# paw.net
KiCad netlist of a schematic drawn in EAGLE
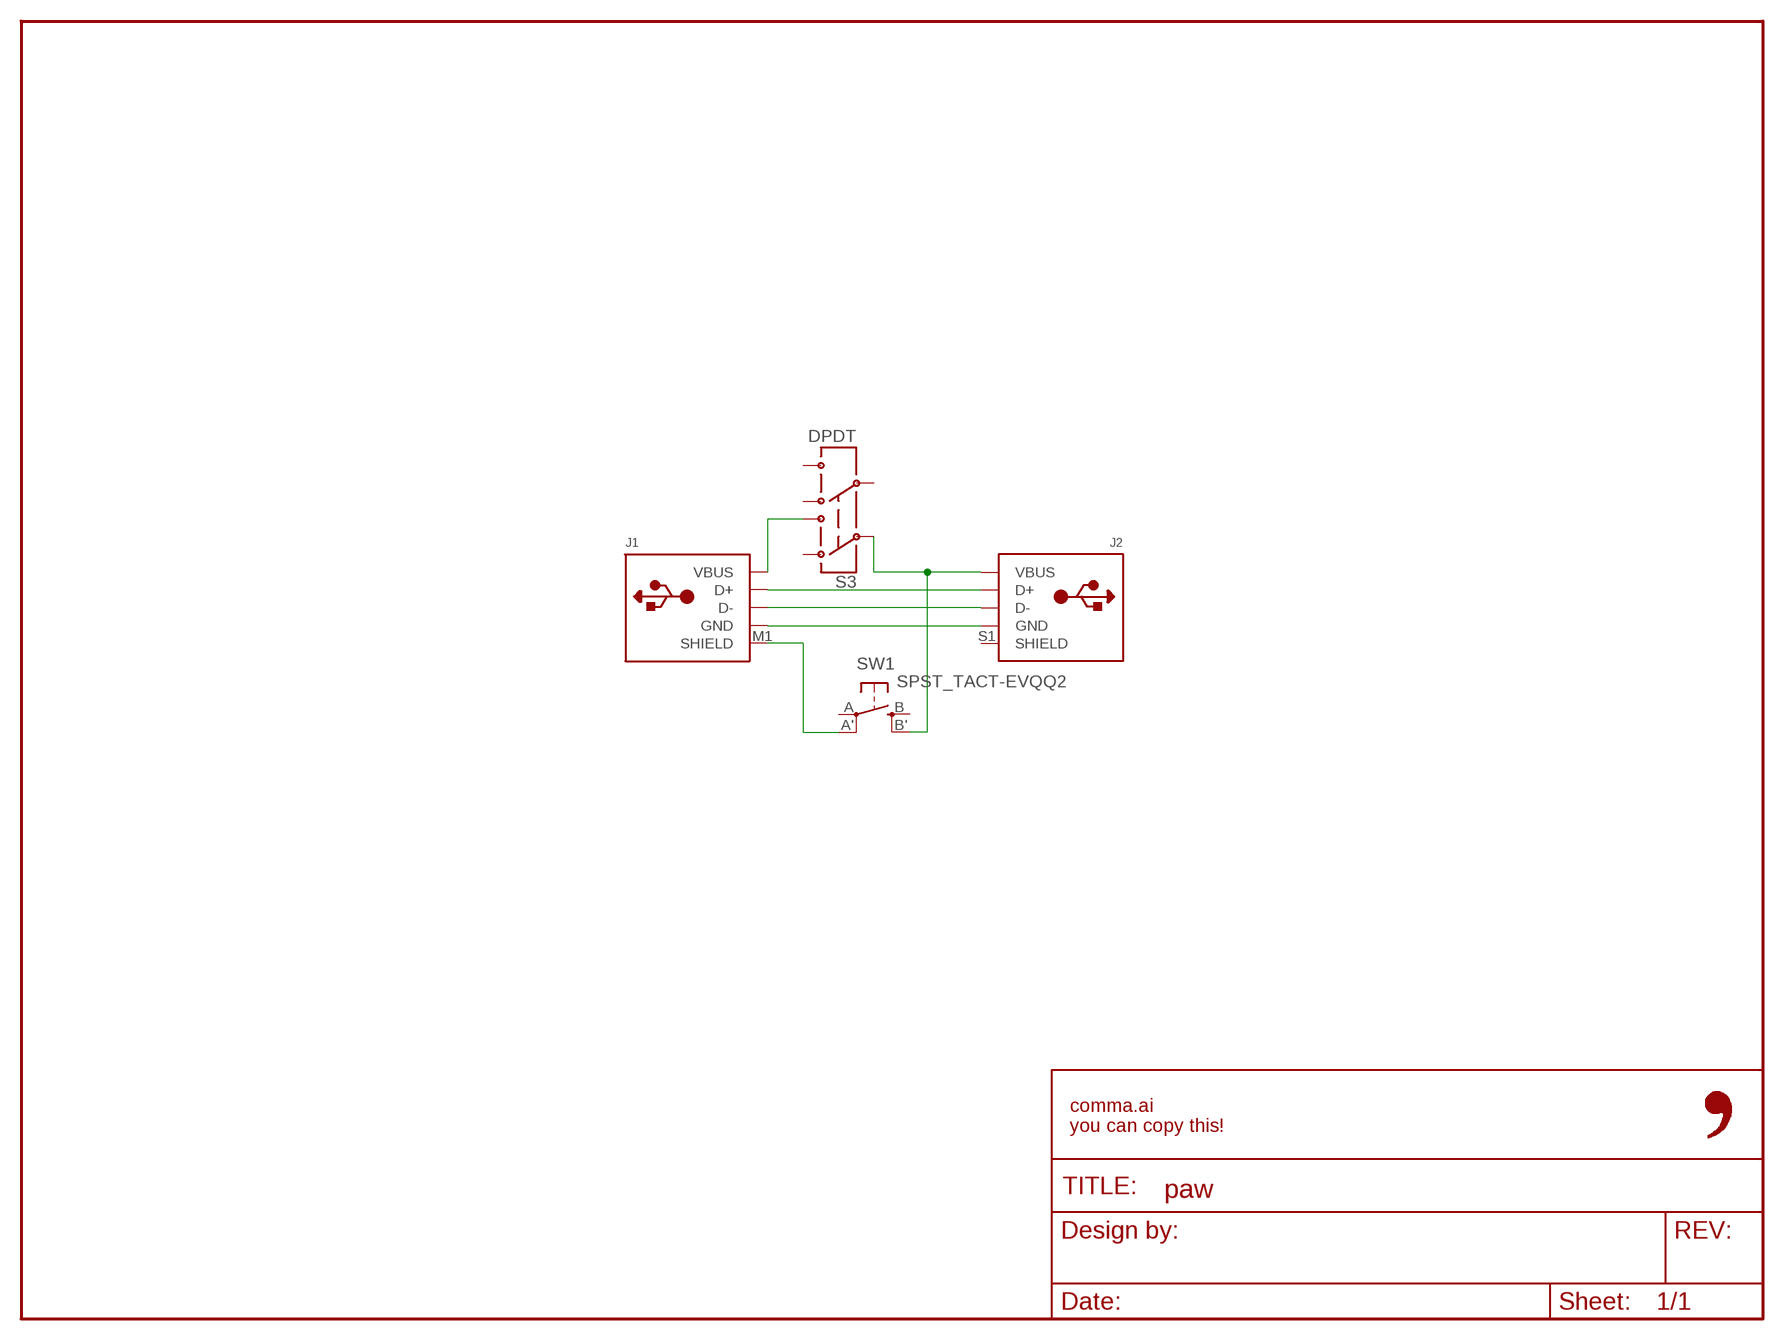
[diagram p0: schematic, sheet 1]

(export (version "E")
  (design (tool "Eeschema 10.0.6"))
  (components
    (comp (ref "FRAME1")
      (value "FRAME-LETTER-OPENNO_PACKAGE")
      (footprint "eagle-import:DUMMY")
      (fields (field (name "DESIGNER") "Nobody"))
      (libsource (lib "eagle-import") (part "FRAME-LETTER-OPENNO_PACKAGE"))
    )
    (comp (ref "J1")
      (value "USB-AA-M")
      (footprint "eagle-import:MOLEX_480371000")
      (libsource (lib "eagle-import") (part "USB-AA-M"))
    )
    (comp (ref "J2")
      (value "USB-MINIBSMD")
      (footprint "eagle-import:USB-MINIB")
      (libsource (lib "eagle-import") (part "USB-MINIBSMD"))
    )
    (comp (ref "S3")
      (value "DPDT")
      (footprint "eagle-import:AYZ0202")
      (libsource (lib "eagle-import") (part "DPDTDPDT"))
    )
    (comp (ref "SW1")
      (value "SPST_TACT-EVQQ2")
      (footprint "eagle-import:EVQ-Q2")
      (libsource (lib "eagle-import") (part "SPST_TACT-EVQQ2"))
    )
  )
  (nets
    (net (code "1") (name "Net-(J1-D+)") (class "Default")
      (node (ref "J1") (pin "3") (pinfunction "D+_3") (pintype "bidirectional"))
      (node (ref "J2") (pin "D+") (pinfunction "D+_D+") (pintype "bidirectional"))
    )
    (net (code "2") (name "Net-(J1-D-)") (class "Default")
      (node (ref "J1") (pin "2") (pinfunction "D-_2") (pintype "bidirectional"))
      (node (ref "J2") (pin "D-") (pinfunction "D-_D-") (pintype "bidirectional"))
    )
    (net (code "3") (name "Net-(J1-GND)") (class "Default")
      (node (ref "J1") (pin "4") (pinfunction "GND_4") (pintype "power_in"))
      (node (ref "J2") (pin "GND") (pinfunction "GND_GND") (pintype "power_in"))
    )
    (net (code "4") (name "Net-(J1-SHIELD)") (class "Default")
      (node (ref "J1") (pin "M1") (pinfunction "SHIELD_M1") (pintype "bidirectional"))
      (node (ref "SW1") (pin "A'") (pinfunction "P1_A'") (pintype "passive"))
    )
    (net (code "5") (name "Net-(J1-VBUS)") (class "Default")
      (node (ref "J1") (pin "1") (pinfunction "VBUS_1") (pintype "power_in"))
      (node (ref "S3") (pin "3") (pinfunction "3_3") (pintype "bidirectional"))
    )
    (net (code "6") (name "Net-(SW1-S1)") (class "Default")
      (node (ref "J2") (pin "VBUS") (pinfunction "VBUS_VBUS") (pintype "power_in"))
      (node (ref "S3") (pin "2") (pinfunction "2_2") (pintype "bidirectional"))
      (node (ref "SW1") (pin "B'") (pinfunction "S1_B'") (pintype "passive"))
    )
    (net (code "7") (name "unconnected-(J2-SHIELD-PadS1)") (class "Default")
      (node (ref "J2") (pin "S1") (pinfunction "SHIELD_S1") (pintype "bidirectional"))
    )
    (net (code "8") (name "unconnected-(S3-Pad1)") (class "Default")
      (node (ref "S3") (pin "1") (pinfunction "1_1") (pintype "bidirectional"))
    )
    (net (code "9") (name "unconnected-(S3-Pad4)") (class "Default")
      (node (ref "S3") (pin "4") (pinfunction "4_4") (pintype "bidirectional"))
    )
    (net (code "10") (name "unconnected-(S3-Pad5)") (class "Default")
      (node (ref "S3") (pin "5") (pinfunction "5_5") (pintype "bidirectional"))
    )
    (net (code "11") (name "unconnected-(S3-Pad6)") (class "Default")
      (node (ref "S3") (pin "6") (pinfunction "6_6") (pintype "bidirectional"))
    )
    (net (code "12") (name "unconnected-(SW1-P-PadA)") (class "Default")
      (node (ref "SW1") (pin "A") (pinfunction "P_A") (pintype "passive"))
    )
    (net (code "13") (name "unconnected-(SW1-S-PadB)") (class "Default")
      (node (ref "SW1") (pin "B") (pinfunction "S_B") (pintype "passive"))
    )
  )
)
